# PowerMonitor.net
KiCad netlist of a schematic drawn in Altium Designer
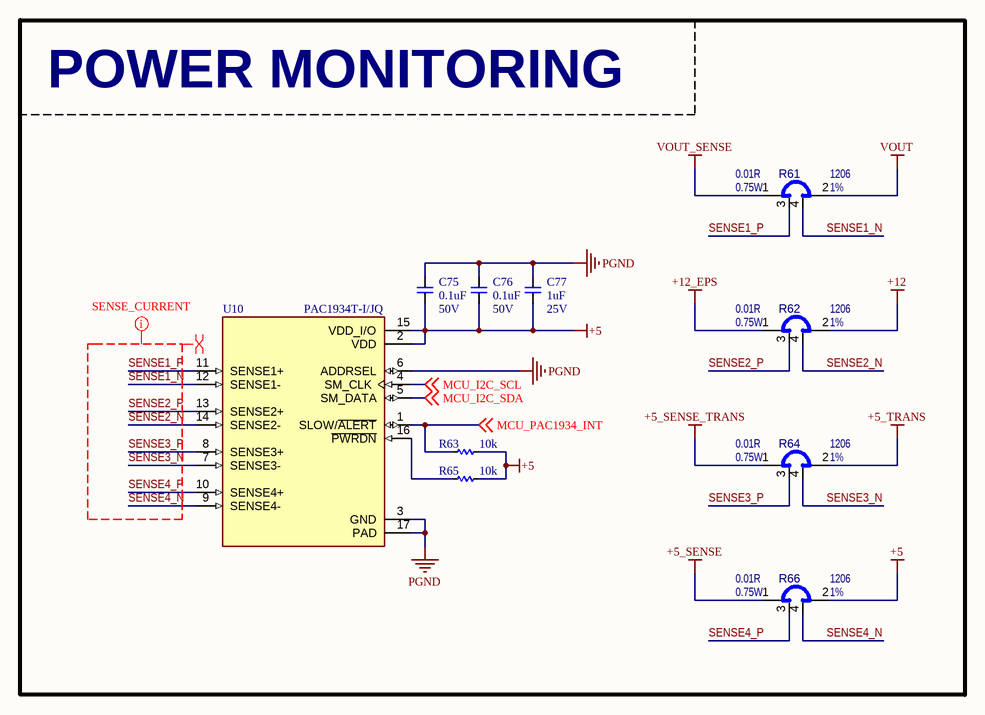
[diagram p0: PowerMonitor.SchDoc]

(export (version "E")
  (design (tool "Eeschema 10.0.6"))
  (components
    (comp (ref "C75")
      (value "0.1uF")
      (footprint "CAP_C_1608X80")
      (description "CAP")
      (fields (field (name "VOLTAGE") "50V"))
      (libsource (lib "LABLIB") (part "_CAP_C_2"))
    )
    (comp (ref "C76")
      (value "0.1uF")
      (footprint "CAP_C_1608X80")
      (description "CAP")
      (fields (field (name "VOLTAGE") "50V"))
      (libsource (lib "LABLIB") (part "_CAP_C_2"))
    )
    (comp (ref "C77")
      (value "1uF")
      (footprint "CAP_C_1608X80")
      (description "CAP")
      (fields (field (name "VOLTAGE") "25V"))
      (libsource (lib "LABLIB") (part "_CAP_C_2"))
    )
    (comp (ref "R61")
      (value "0.01R")
      (footprint "RES_C_1206_SHUNT")
      (description "Shunt")
      (fields
        (field (name "PACKAGE") "1206")
        (field (name "TOLERANCE") "1%")
        (field (name "POWER") "0.75W")
        (field (name "Comment") "Shunt 4 Pin")
        (field (name "OWNER") "Ciprian Abramov")
      )
      (libsource (lib "LABLIB") (part "RSMT1316"))
    )
    (comp (ref "R62")
      (value "0.01R")
      (footprint "RES_C_1206_SHUNT")
      (description "Shunt")
      (fields
        (field (name "PACKAGE") "1206")
        (field (name "TOLERANCE") "1%")
        (field (name "POWER") "0.75W")
        (field (name "Comment") "Shunt 4 Pin")
        (field (name "OWNER") "Ciprian Abramov")
      )
      (libsource (lib "LABLIB") (part "RSMT1316"))
    )
    (comp (ref "R63")
      (value "10k")
      (footprint "RES_C_1608X60")
      (description "RES")
      (libsource (lib "LABLIB") (part "_RES_B_2_2"))
    )
    (comp (ref "R64")
      (value "0.01R")
      (footprint "RES_C_1206_SHUNT")
      (description "Shunt")
      (fields
        (field (name "PACKAGE") "1206")
        (field (name "TOLERANCE") "1%")
        (field (name "POWER") "0.75W")
        (field (name "Comment") "Shunt 4 Pin")
        (field (name "OWNER") "Ciprian Abramov")
      )
      (libsource (lib "LABLIB") (part "RSMT1316"))
    )
    (comp (ref "R65")
      (value "10k")
      (footprint "RES_C_1608X60")
      (description "RES")
      (libsource (lib "LABLIB") (part "_RES_B_2_2"))
    )
    (comp (ref "R66")
      (value "0.01R")
      (footprint "RES_C_1206_SHUNT")
      (description "Shunt")
      (fields
        (field (name "PACKAGE") "1206")
        (field (name "TOLERANCE") "1%")
        (field (name "POWER") "0.75W")
        (field (name "Comment") "Shunt 4 Pin")
        (field (name "OWNER") "Ciprian Abramov")
      )
      (libsource (lib "LABLIB") (part "RSMT1316"))
    )
    (comp (ref "U10")
      (value "PAC1934T-I/JQ")
      (footprint "QFN65")
      (libsource (lib "new1") (part "PAC1934T-I/JQ"))
    )
  )
  (nets
    (net (code "1") (name "+5") (class "Default")
      (node (ref "C75") (pin "2") (pinfunction "2_2") (pintype "passive"))
      (node (ref "C76") (pin "2") (pinfunction "2_2") (pintype "passive"))
      (node (ref "C77") (pin "2") (pinfunction "2_2") (pintype "passive"))
      (node (ref "R63") (pin "1") (pinfunction "1_1") (pintype "passive"))
      (node (ref "R65") (pin "2") (pinfunction "2_2") (pintype "passive"))
      (node (ref "R66") (pin "2") (pinfunction "2_2") (pintype "passive"))
      (node (ref "U10") (pin "15") (pinfunction "VDD_I/O_15") (pintype "power_in"))
      (node (ref "U10") (pin "2") (pinfunction "VDD_2") (pintype "power_in"))
    )
    (net (code "2") (name "+5_SENSE") (class "Default")
      (node (ref "R66") (pin "1") (pinfunction "1_1") (pintype "passive"))
    )
    (net (code "3") (name "+5_SENSE_TRANS") (class "Default")
      (node (ref "R64") (pin "1") (pinfunction "1_1") (pintype "passive"))
    )
    (net (code "4") (name "+5_TRANS") (class "Default")
      (node (ref "R64") (pin "2") (pinfunction "2_2") (pintype "passive"))
    )
    (net (code "5") (name "+12") (class "Default")
      (node (ref "R62") (pin "2") (pinfunction "2_2") (pintype "passive"))
    )
    (net (code "6") (name "+12_EPS") (class "Default")
      (node (ref "R62") (pin "1") (pinfunction "1_1") (pintype "passive"))
    )
    (net (code "7") (name "/SENSE1_N") (class "Default")
      (node (ref "R61") (pin "4") (pinfunction "4_4") (pintype "passive"))
      (node (ref "U10") (pin "12") (pinfunction "SENSE1-_12") (pintype "input"))
    )
    (net (code "8") (name "/SENSE1_P") (class "Default")
      (node (ref "R61") (pin "3") (pinfunction "3_3") (pintype "passive"))
      (node (ref "U10") (pin "11") (pinfunction "SENSE1+_11") (pintype "input"))
    )
    (net (code "9") (name "/SENSE2_N") (class "Default")
      (node (ref "R62") (pin "4") (pinfunction "4_4") (pintype "passive"))
      (node (ref "U10") (pin "14") (pinfunction "SENSE2-_14") (pintype "input"))
    )
    (net (code "10") (name "/SENSE2_P") (class "Default")
      (node (ref "R62") (pin "3") (pinfunction "3_3") (pintype "passive"))
      (node (ref "U10") (pin "13") (pinfunction "SENSE2+_13") (pintype "input"))
    )
    (net (code "11") (name "/SENSE3_N") (class "Default")
      (node (ref "R64") (pin "4") (pinfunction "4_4") (pintype "passive"))
      (node (ref "U10") (pin "7") (pinfunction "SENSE3-_7") (pintype "input"))
    )
    (net (code "12") (name "/SENSE3_P") (class "Default")
      (node (ref "R64") (pin "3") (pinfunction "3_3") (pintype "passive"))
      (node (ref "U10") (pin "8") (pinfunction "SENSE3+_8") (pintype "input"))
    )
    (net (code "13") (name "/SENSE4_N") (class "Default")
      (node (ref "R66") (pin "4") (pinfunction "4_4") (pintype "passive"))
      (node (ref "U10") (pin "9") (pinfunction "SENSE4-_9") (pintype "input"))
    )
    (net (code "14") (name "/SENSE4_P") (class "Default")
      (node (ref "R66") (pin "3") (pinfunction "3_3") (pintype "passive"))
      (node (ref "U10") (pin "10") (pinfunction "SENSE4+_10") (pintype "input"))
    )
    (net (code "15") (name "MCU_I2C_SCL") (class "Default")
      (node (ref "U10") (pin "4") (pinfunction "SM_CLK_4") (pintype "input"))
    )
    (net (code "16") (name "MCU_I2C_SDA") (class "Default")
      (node (ref "U10") (pin "5") (pinfunction "SM_DATA_5") (pintype "bidirectional"))
    )
    (net (code "17") (name "MCU_PAC1934_INT") (class "Default")
      (node (ref "R63") (pin "2") (pinfunction "2_2") (pintype "passive"))
      (node (ref "U10") (pin "1") (pinfunction "SLOW/~{ALERT}_1") (pintype "bidirectional"))
    )
    (net (code "18") (name "Net-(U10-~{PWRDN})") (class "Default")
      (node (ref "R65") (pin "1") (pinfunction "1_1") (pintype "passive"))
      (node (ref "U10") (pin "16") (pinfunction "~{PWRDN}_16") (pintype "input"))
    )
    (net (code "19") (name "PGND") (class "Default")
      (node (ref "C75") (pin "1") (pinfunction "1_1") (pintype "passive"))
      (node (ref "C76") (pin "1") (pinfunction "1_1") (pintype "passive"))
      (node (ref "C77") (pin "1") (pinfunction "1_1") (pintype "passive"))
      (node (ref "U10") (pin "17") (pinfunction "PAD_17") (pintype "passive"))
      (node (ref "U10") (pin "3") (pinfunction "GND_3") (pintype "power_in"))
      (node (ref "U10") (pin "6") (pinfunction "ADDRSEL_6") (pintype "bidirectional"))
    )
    (net (code "20") (name "VOUT") (class "Default")
      (node (ref "R61") (pin "2") (pinfunction "2_2") (pintype "passive"))
    )
    (net (code "21") (name "VOUT_SENSE") (class "Default")
      (node (ref "R61") (pin "1") (pinfunction "1_1") (pintype "passive"))
    )
  )
)
